# source_eagle.net
KiCad netlist of a schematic drawn in EAGLE
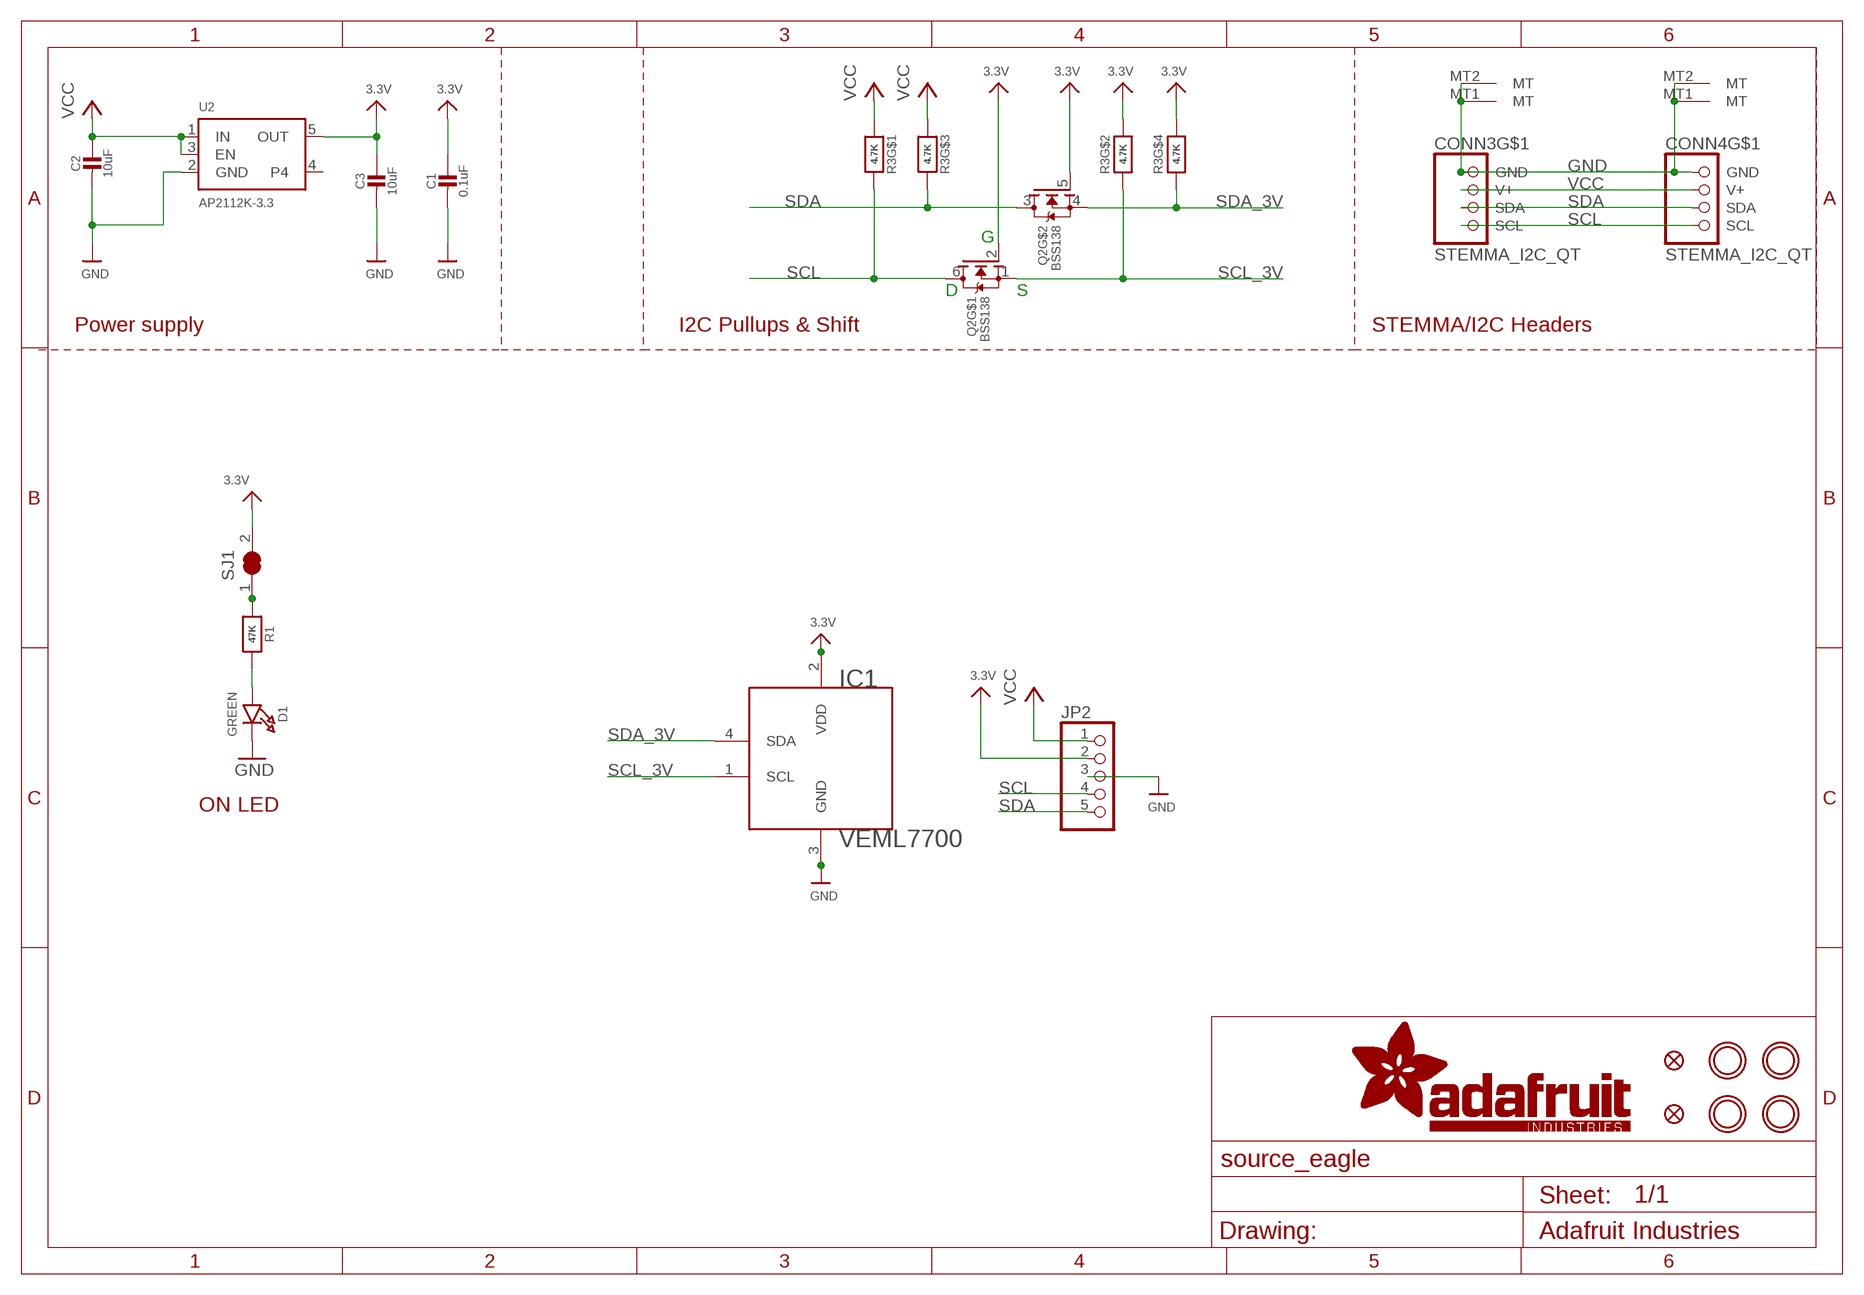
[diagram p0: schematic, sheet 1]

(export (version "E")
  (design (tool "Eeschema 10.0.6"))
  (components
    (comp (ref "C1")
      (value "0.1uF")
      (footprint "eagle-import:0603-NO")
      (libsource (lib "eagle-import") (part "CAP_CERAMIC0603_NO"))
    )
    (comp (ref "C2")
      (value "10uF")
      (footprint "eagle-import:0805-NO")
      (libsource (lib "eagle-import") (part "CAP_CERAMIC0805-NOOUTLINE"))
    )
    (comp (ref "C3")
      (value "10uF")
      (footprint "eagle-import:0805-NO")
      (libsource (lib "eagle-import") (part "CAP_CERAMIC0805-NOOUTLINE"))
    )
    (comp (ref "CONN3")
      (value "STEMMA_I2C_QT")
      (footprint "eagle-import:JST_SH4")
      (libsource (lib "eagle-import") (part "STEMMA_I2C_QT"))
    )
    (comp (ref "CONN4")
      (value "STEMMA_I2C_QT")
      (footprint "eagle-import:JST_SH4")
      (libsource (lib "eagle-import") (part "STEMMA_I2C_QT"))
    )
    (comp (ref "D1")
      (value "GREEN")
      (footprint "eagle-import:CHIPLED_0603_NOOUTLINE")
      (libsource (lib "eagle-import") (part "LED0603_NOOUTLINE"))
    )
    (comp (ref "FID3")
      (value "FIDUCIAL_1MM")
      (footprint "eagle-import:FIDUCIAL_1MM")
      (libsource (lib "eagle-import") (part "FIDUCIAL_1MM"))
    )
    (comp (ref "FID4")
      (value "FIDUCIAL_1MM")
      (footprint "eagle-import:FIDUCIAL_1MM")
      (libsource (lib "eagle-import") (part "FIDUCIAL_1MM"))
    )
    (comp (ref "IC1")
      (value "VEML7700")
      (footprint "eagle-import:VEML7700")
      (libsource (lib "eagle-import") (part "VEML7700"))
    )
    (comp (ref "JP2")
      (value "HEADER-1X5ROUND")
      (footprint "eagle-import:1X05_ROUND")
      (libsource (lib "eagle-import") (part "HEADER-1X5ROUND"))
    )
    (comp (ref "Q2")
      (value "BSS138")
      (footprint "eagle-import:SOT363")
      (libsource (lib "eagle-import") (part "MOSFET-N_DUAL"))
    )
    (comp (ref "R1")
      (value "47K")
      (footprint "eagle-import:0603-NO")
      (libsource (lib "eagle-import") (part "RESISTOR_0603_NOOUT"))
    )
    (comp (ref "R3")
      (value "4.7K")
      (footprint "eagle-import:RESPACK_4X0603")
      (libsource (lib "eagle-import") (part "RESISTOR_4PACK"))
    )
    (comp (ref "SJ1")
      (value "SOLDERJUMPER_CLOSED")
      (footprint "eagle-import:SOLDERJUMPER_CLOSEDWIRE")
      (libsource (lib "eagle-import") (part "SOLDERJUMPER_CLOSED"))
    )
    (comp (ref "U$1")
      (value "MOUNTINGHOLE2.5")
      (footprint "eagle-import:MOUNTINGHOLE_2.5_PLATED")
      (libsource (lib "eagle-import") (part "MOUNTINGHOLE2.5"))
    )
    (comp (ref "U$17")
      (value "MOUNTINGHOLE2.5")
      (footprint "eagle-import:MOUNTINGHOLE_2.5_PLATED")
      (libsource (lib "eagle-import") (part "MOUNTINGHOLE2.5"))
    )
    (comp (ref "U$19")
      (value "MOUNTINGHOLE2.5")
      (footprint "eagle-import:MOUNTINGHOLE_2.5_PLATED")
      (libsource (lib "eagle-import") (part "MOUNTINGHOLE2.5"))
    )
    (comp (ref "U$21")
      (value "MOUNTINGHOLE2.5")
      (footprint "eagle-import:MOUNTINGHOLE_2.5_PLATED")
      (libsource (lib "eagle-import") (part "MOUNTINGHOLE2.5"))
    )
    (comp (ref "U2")
      (value "AP2112K-3.3")
      (footprint "eagle-import:SOT23-5")
      (libsource (lib "eagle-import") (part "VREG_SOT23-5"))
    )
  )
  (nets
    (net (code "1") (name "/SCL") (class "Default")
      (node (ref "CONN3") (pin "4") (pinfunction "SCL_4") (pintype "passive"))
      (node (ref "CONN4") (pin "4") (pinfunction "SCL_4") (pintype "passive"))
      (node (ref "JP2") (pin "4") (pinfunction "4_4") (pintype "passive"))
      (node (ref "Q2") (pin "6") (pinfunction "D_6") (pintype "bidirectional"))
      (node (ref "R3") (pin "8") (pinfunction "2_8") (pintype "passive"))
    )
    (net (code "2") (name "/SCL_3V") (class "Default")
      (node (ref "IC1") (pin "1") (pinfunction "SCL_1") (pintype "bidirectional"))
      (node (ref "Q2") (pin "1") (pinfunction "S_1") (pintype "bidirectional"))
      (node (ref "R3") (pin "7") (pinfunction "2_7") (pintype "passive"))
    )
    (net (code "3") (name "/SDA") (class "Default")
      (node (ref "CONN3") (pin "3") (pinfunction "SDA_3") (pintype "passive"))
      (node (ref "CONN4") (pin "3") (pinfunction "SDA_3") (pintype "passive"))
      (node (ref "JP2") (pin "5") (pinfunction "5_5") (pintype "passive"))
      (node (ref "Q2") (pin "3") (pinfunction "D_3") (pintype "bidirectional"))
      (node (ref "R3") (pin "6") (pinfunction "2_6") (pintype "passive"))
    )
    (net (code "4") (name "/SDA_3V") (class "Default")
      (node (ref "IC1") (pin "4") (pinfunction "SDA_4") (pintype "bidirectional"))
      (node (ref "Q2") (pin "4") (pinfunction "S_4") (pintype "bidirectional"))
      (node (ref "R3") (pin "5") (pinfunction "2_5") (pintype "passive"))
    )
    (net (code "5") (name "3.3V") (class "Default")
      (node (ref "C1") (pin "1") (pinfunction "1_1") (pintype "passive"))
      (node (ref "C3") (pin "1") (pinfunction "1_1") (pintype "passive"))
      (node (ref "IC1") (pin "2") (pinfunction "VDD_2") (pintype "power_in"))
      (node (ref "JP2") (pin "2") (pinfunction "2_2") (pintype "passive"))
      (node (ref "Q2") (pin "2") (pinfunction "G_2") (pintype "bidirectional"))
      (node (ref "Q2") (pin "5") (pinfunction "G_5") (pintype "bidirectional"))
      (node (ref "R3") (pin "2") (pinfunction "1_2") (pintype "passive"))
      (node (ref "R3") (pin "4") (pinfunction "1_4") (pintype "passive"))
      (node (ref "SJ1") (pin "2") (pinfunction "2_2") (pintype "passive"))
      (node (ref "U2") (pin "5") (pinfunction "OUT_5") (pintype "power_in"))
    )
    (net (code "6") (name "GND") (class "Default")
      (node (ref "C1") (pin "2") (pinfunction "2_2") (pintype "passive"))
      (node (ref "C2") (pin "2") (pinfunction "2_2") (pintype "passive"))
      (node (ref "C3") (pin "2") (pinfunction "2_2") (pintype "passive"))
      (node (ref "CONN3") (pin "1") (pinfunction "GND_1") (pintype "passive"))
      (node (ref "CONN3") (pin "MT1") (pinfunction "MT_MT1") (pintype "bidirectional"))
      (node (ref "CONN3") (pin "MT2") (pinfunction "MT_MT2") (pintype "bidirectional"))
      (node (ref "CONN4") (pin "1") (pinfunction "GND_1") (pintype "passive"))
      (node (ref "CONN4") (pin "MT1") (pinfunction "MT_MT1") (pintype "bidirectional"))
      (node (ref "CONN4") (pin "MT2") (pinfunction "MT_MT2") (pintype "bidirectional"))
      (node (ref "D1") (pin "C") (pinfunction "C_C") (pintype "passive"))
      (node (ref "IC1") (pin "3") (pinfunction "GND_3") (pintype "power_in"))
      (node (ref "JP2") (pin "3") (pinfunction "3_3") (pintype "passive"))
      (node (ref "U2") (pin "2") (pinfunction "GND_2") (pintype "power_in"))
    )
    (net (code "7") (name "Net-(D1-PadA)") (class "Default")
      (node (ref "D1") (pin "A") (pinfunction "A_A") (pintype "passive"))
      (node (ref "R1") (pin "2") (pinfunction "2_2") (pintype "passive"))
    )
    (net (code "8") (name "Net-(R1-Pad1)") (class "Default")
      (node (ref "R1") (pin "1") (pinfunction "1_1") (pintype "passive"))
      (node (ref "SJ1") (pin "1") (pinfunction "1_1") (pintype "passive"))
    )
    (net (code "9") (name "VCC") (class "Default")
      (node (ref "C2") (pin "1") (pinfunction "1_1") (pintype "passive"))
      (node (ref "CONN3") (pin "2") (pinfunction "V+_2") (pintype "passive"))
      (node (ref "CONN4") (pin "2") (pinfunction "V+_2") (pintype "passive"))
      (node (ref "JP2") (pin "1") (pinfunction "1_1") (pintype "passive"))
      (node (ref "R3") (pin "1") (pinfunction "1_1") (pintype "passive"))
      (node (ref "R3") (pin "3") (pinfunction "1_3") (pintype "passive"))
      (node (ref "U2") (pin "1") (pinfunction "IN_1") (pintype "power_in"))
      (node (ref "U2") (pin "3") (pinfunction "EN_3") (pintype "input"))
    )
    (net (code "10") (name "unconnected-(U2-P4-Pad4)") (class "Default")
      (node (ref "U2") (pin "4") (pinfunction "P4_4") (pintype "bidirectional"))
    )
  )
)
